# XBee-Explorer-Dongle-v14.net
KiCad netlist of a schematic drawn in EAGLE
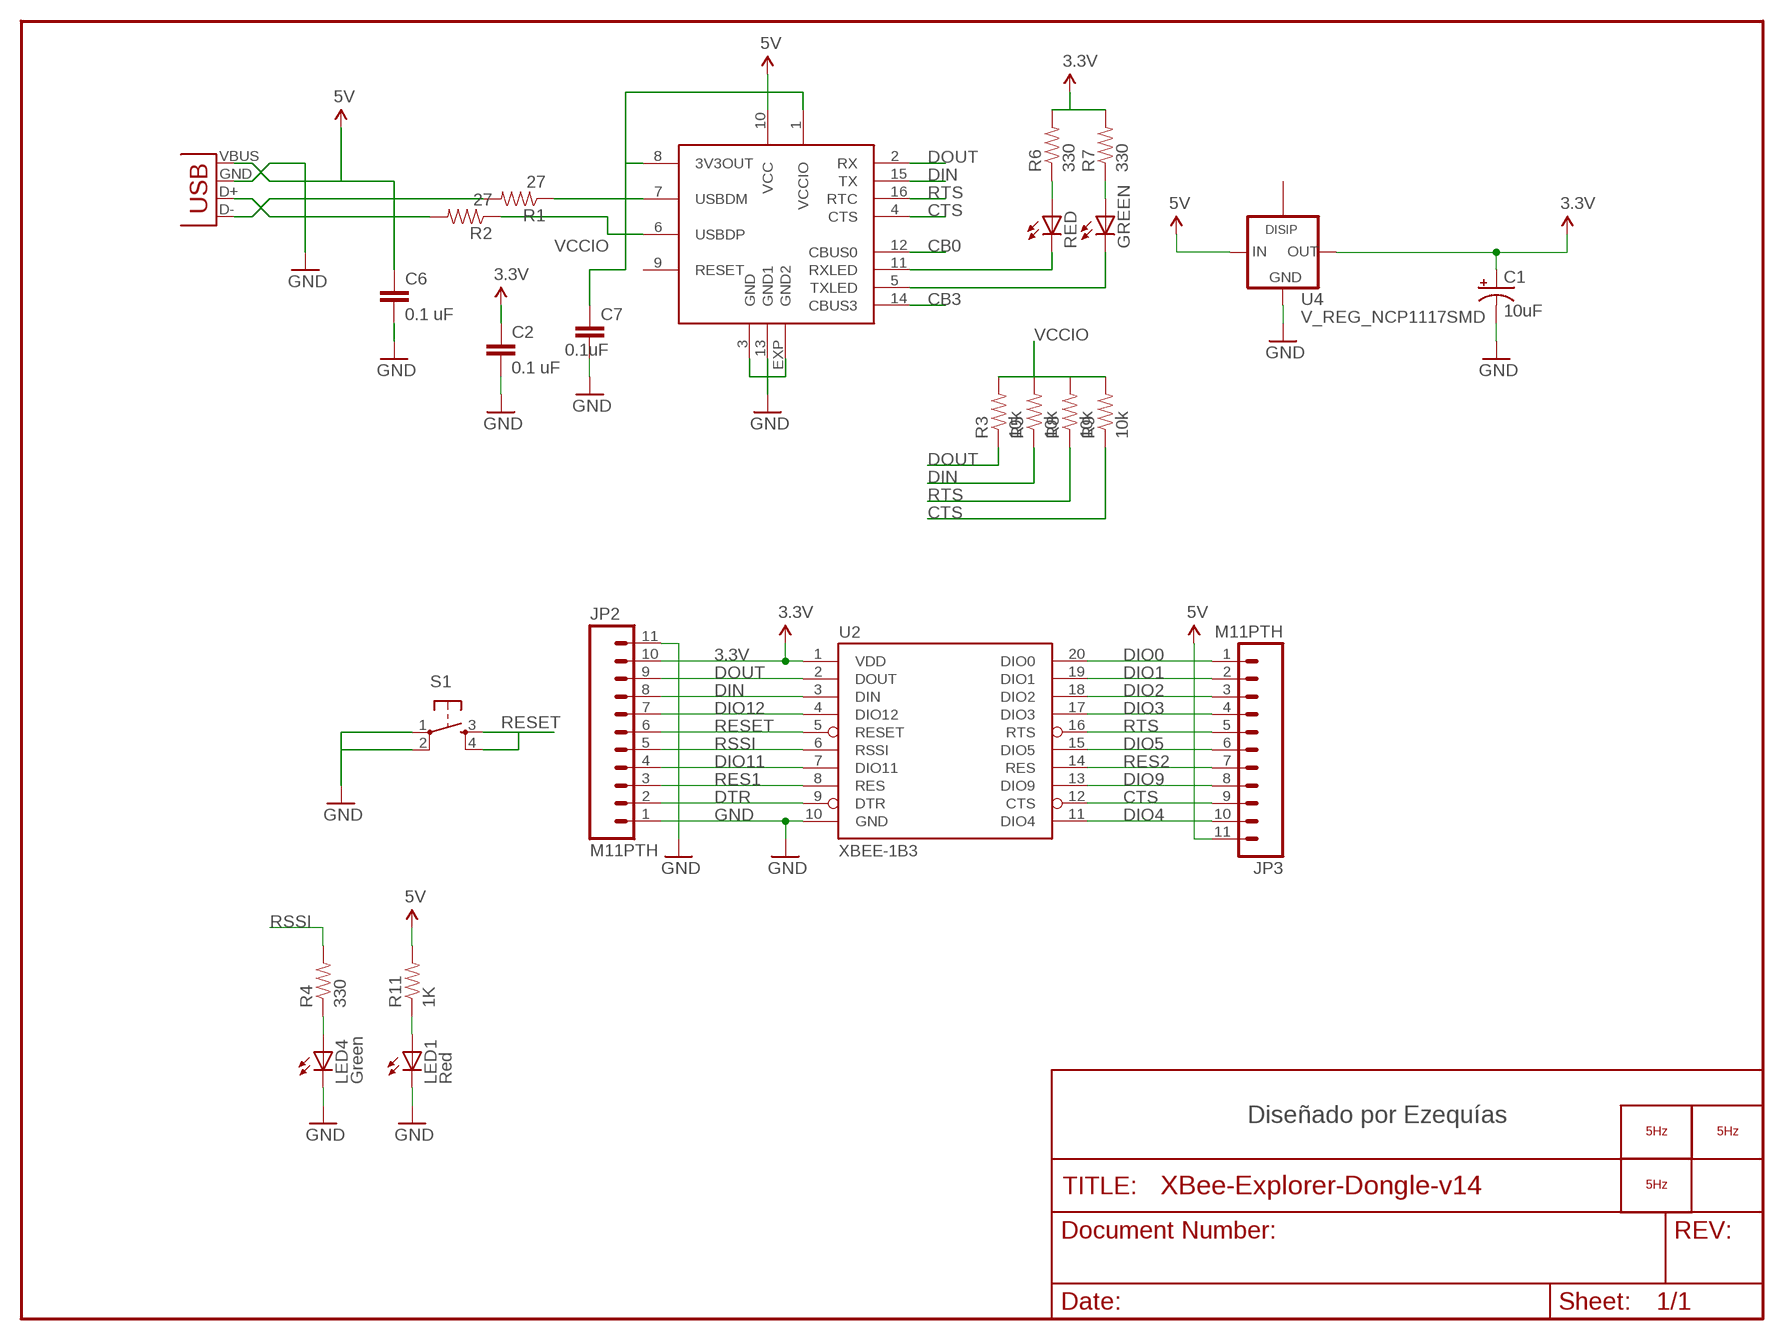
[diagram p0: schematic, sheet 1]

(export (version "E")
  (design (tool "Eeschema 10.0.6"))
  (components
    (comp (ref "C1")
      (value "10uF")
      (footprint "eagle-import:EIA3216")
      (libsource (lib "eagle-import") (part "CAP_POL1206"))
    )
    (comp (ref "C2")
      (value "0.1 uF")
      (footprint "eagle-import:0603-CAP")
      (libsource (lib "eagle-import") (part "CAP0603-CAP"))
    )
    (comp (ref "C6")
      (value "0.1 uF")
      (footprint "eagle-import:0603-CAP")
      (libsource (lib "eagle-import") (part "CAP0603-CAP"))
    )
    (comp (ref "C7")
      (value "0.1uF")
      (footprint "eagle-import:0603-CAP")
      (libsource (lib "eagle-import") (part "CAP0603-CAP"))
    )
    (comp (ref "GREEN")
      (value "LED0603")
      (footprint "eagle-import:LED-0603")
      (libsource (lib "eagle-import") (part "LED0603"))
    )
    (comp (ref "JP2")
      (value "M11PTH")
      (footprint "eagle-import:1X11")
      (libsource (lib "eagle-import") (part "M11PTH"))
    )
    (comp (ref "JP3")
      (value "M11PTH")
      (footprint "eagle-import:1X11")
      (libsource (lib "eagle-import") (part "M11PTH"))
    )
    (comp (ref "LED1")
      (value "Red")
      (footprint "eagle-import:LED-0603")
      (libsource (lib "eagle-import") (part "LED0603"))
    )
    (comp (ref "LED4")
      (value "Green")
      (footprint "eagle-import:LED-0603")
      (libsource (lib "eagle-import") (part "LED0603"))
    )
    (comp (ref "LOGO2")
      (value "LOGO_5HZ_H_10MM")
      (footprint "eagle-import:5HZ_LOGO_H_10MM")
      (libsource (lib "eagle-import") (part "LOGO_5HZ_H_10MM"))
    )
    (comp (ref "LOGO3")
      (value "LOGO_5HZ_H_COOPER_15MM")
      (footprint "eagle-import:5HZ_LOGO_H_COOPER_15MM")
      (libsource (lib "eagle-import") (part "LOGO_5HZ_H_COOPER_15MM"))
    )
    (comp (ref "LOGO4")
      (value "LOGO_5HZ_WEB_COOPER_10MM")
      (footprint "eagle-import:5HZ_WEB_COOPER_10MM")
      (libsource (lib "eagle-import") (part "LOGO_5HZ_WEB_COOPER_10MM"))
    )
    (comp (ref "R1")
      (value "27")
      (footprint "eagle-import:0603-RES")
      (libsource (lib "eagle-import") (part "RESISTOR0603-RES"))
    )
    (comp (ref "R2")
      (value "27")
      (footprint "eagle-import:0603-RES")
      (libsource (lib "eagle-import") (part "RESISTOR0603-RES"))
    )
    (comp (ref "R3")
      (value "10k")
      (footprint "eagle-import:0603-RES")
      (libsource (lib "eagle-import") (part "RESISTOR0603-RES"))
    )
    (comp (ref "R4")
      (value "330")
      (footprint "eagle-import:0603-RES")
      (libsource (lib "eagle-import") (part "RESISTOR0603-RES"))
    )
    (comp (ref "R5")
      (value "10k")
      (footprint "eagle-import:0603-RES")
      (libsource (lib "eagle-import") (part "RESISTOR0603-RES"))
    )
    (comp (ref "R6")
      (value "330")
      (footprint "eagle-import:0603-RES")
      (libsource (lib "eagle-import") (part "RESISTOR0603-RES"))
    )
    (comp (ref "R7")
      (value "330")
      (footprint "eagle-import:0603-RES")
      (libsource (lib "eagle-import") (part "RESISTOR0603-RES"))
    )
    (comp (ref "R8")
      (value "10k")
      (footprint "eagle-import:0603-RES")
      (libsource (lib "eagle-import") (part "RESISTOR0603-RES"))
    )
    (comp (ref "R9")
      (value "10k")
      (footprint "eagle-import:0603-RES")
      (libsource (lib "eagle-import") (part "RESISTOR0603-RES"))
    )
    (comp (ref "R11")
      (value "1K")
      (footprint "eagle-import:0603-RES")
      (libsource (lib "eagle-import") (part "RESISTOR0603-RES"))
    )
    (comp (ref "RED")
      (value "LED0603")
      (footprint "eagle-import:LED-0603")
      (libsource (lib "eagle-import") (part "LED0603"))
    )
    (comp (ref "S1")
      (value "TAC_SWITCHSMD")
      (footprint "eagle-import:TACTILE_SWITCH_SMD")
      (libsource (lib "eagle-import") (part "TAC_SWITCHSMD"))
    )
    (comp (ref "U$5")
      (value "FT230")
      (footprint "eagle-import:QFN-16")
      (libsource (lib "eagle-import") (part "FT230"))
    )
    (comp (ref "U2")
      (value "XBEE-1B3")
      (footprint "eagle-import:XBEE-SMD")
      (libsource (lib "eagle-import") (part "XBEE-1B3"))
    )
    (comp (ref "U4")
      (value "V_REG_NCP1117SMD")
      (footprint "eagle-import:SOT223")
      (libsource (lib "eagle-import") (part "V_REG_NCP1117SMD"))
    )
    (comp (ref "X2")
      (value "USB-A-H")
      (footprint "eagle-import:USB-A-H")
      (libsource (lib "eagle-import") (part "USB-A-H"))
    )
  )
  (nets
    (net (code "1") (name "/CB0") (class "Default")
      (node (ref "U$5") (pin "12") (pinfunction "CBUS0_12") (pintype "bidirectional"))
    )
    (net (code "2") (name "/CB3") (class "Default")
      (node (ref "U$5") (pin "14") (pinfunction "CBUS3_14") (pintype "bidirectional"))
    )
    (net (code "3") (name "/CTS") (class "Default")
      (node (ref "JP3") (pin "9") (pinfunction "9_9") (pintype "passive"))
      (node (ref "R9") (pin "1") (pinfunction "1_1") (pintype "passive"))
      (node (ref "U$5") (pin "4") (pinfunction "CTS_4") (pintype "bidirectional"))
      (node (ref "U2") (pin "12") (pinfunction "CTS_12") (pintype "output"))
    )
    (net (code "4") (name "/DIN") (class "Default")
      (node (ref "JP2") (pin "8") (pinfunction "8_8") (pintype "passive"))
      (node (ref "R5") (pin "1") (pinfunction "1_1") (pintype "passive"))
      (node (ref "U$5") (pin "15") (pinfunction "TX_15") (pintype "bidirectional"))
      (node (ref "U2") (pin "3") (pinfunction "DIN_3") (pintype "input"))
    )
    (net (code "5") (name "/DIO0") (class "Default")
      (node (ref "JP3") (pin "1") (pinfunction "1_1") (pintype "passive"))
      (node (ref "U2") (pin "20") (pinfunction "DIO0_20") (pintype "bidirectional"))
    )
    (net (code "6") (name "/DIO1") (class "Default")
      (node (ref "JP3") (pin "2") (pinfunction "2_2") (pintype "passive"))
      (node (ref "U2") (pin "19") (pinfunction "DIO1_19") (pintype "bidirectional"))
    )
    (net (code "7") (name "/DIO2") (class "Default")
      (node (ref "JP3") (pin "3") (pinfunction "3_3") (pintype "passive"))
      (node (ref "U2") (pin "18") (pinfunction "DIO2_18") (pintype "bidirectional"))
    )
    (net (code "8") (name "/DIO3") (class "Default")
      (node (ref "JP3") (pin "4") (pinfunction "4_4") (pintype "passive"))
      (node (ref "U2") (pin "17") (pinfunction "DIO3_17") (pintype "bidirectional"))
    )
    (net (code "9") (name "/DIO4") (class "Default")
      (node (ref "JP3") (pin "10") (pinfunction "10_10") (pintype "passive"))
      (node (ref "U2") (pin "11") (pinfunction "DIO4_11") (pintype "bidirectional"))
    )
    (net (code "10") (name "/DIO5") (class "Default")
      (node (ref "JP3") (pin "6") (pinfunction "6_6") (pintype "passive"))
      (node (ref "U2") (pin "15") (pinfunction "DIO5_15") (pintype "bidirectional"))
    )
    (net (code "11") (name "/DIO9") (class "Default")
      (node (ref "JP3") (pin "8") (pinfunction "8_8") (pintype "passive"))
      (node (ref "U2") (pin "13") (pinfunction "DIO9_13") (pintype "bidirectional"))
    )
    (net (code "12") (name "/DIO11") (class "Default")
      (node (ref "JP2") (pin "4") (pinfunction "4_4") (pintype "passive"))
      (node (ref "U2") (pin "7") (pinfunction "DIO11_7") (pintype "bidirectional"))
    )
    (net (code "13") (name "/DIO12") (class "Default")
      (node (ref "JP2") (pin "7") (pinfunction "7_7") (pintype "passive"))
      (node (ref "U2") (pin "4") (pinfunction "DIO12_4") (pintype "bidirectional"))
    )
    (net (code "14") (name "/DOUT") (class "Default")
      (node (ref "JP2") (pin "9") (pinfunction "9_9") (pintype "passive"))
      (node (ref "R3") (pin "1") (pinfunction "1_1") (pintype "passive"))
      (node (ref "U$5") (pin "2") (pinfunction "RX_2") (pintype "bidirectional"))
      (node (ref "U2") (pin "2") (pinfunction "DOUT_2") (pintype "output"))
    )
    (net (code "15") (name "/DTR") (class "Default")
      (node (ref "JP2") (pin "2") (pinfunction "2_2") (pintype "passive"))
      (node (ref "U2") (pin "9") (pinfunction "DTR_9") (pintype "bidirectional"))
    )
    (net (code "16") (name "/RES1") (class "Default")
      (node (ref "JP2") (pin "3") (pinfunction "3_3") (pintype "passive"))
      (node (ref "U2") (pin "8") (pinfunction "RES_8") (pintype "bidirectional"))
    )
    (net (code "17") (name "/RES2") (class "Default")
      (node (ref "JP3") (pin "7") (pinfunction "7_7") (pintype "passive"))
      (node (ref "U2") (pin "14") (pinfunction "RES_14") (pintype "bidirectional"))
    )
    (net (code "18") (name "/RESET") (class "Default")
      (node (ref "JP2") (pin "6") (pinfunction "6_6") (pintype "passive"))
      (node (ref "S1") (pin "3") (pinfunction "3_3") (pintype "passive"))
      (node (ref "S1") (pin "4") (pinfunction "4_4") (pintype "passive"))
      (node (ref "U2") (pin "5") (pinfunction "RESET_5") (pintype "input"))
    )
    (net (code "19") (name "/RSSI") (class "Default")
      (node (ref "JP2") (pin "5") (pinfunction "5_5") (pintype "passive"))
      (node (ref "R4") (pin "2") (pinfunction "2_2") (pintype "passive"))
      (node (ref "U2") (pin "6") (pinfunction "RSSI_6") (pintype "bidirectional"))
    )
    (net (code "20") (name "/RTS") (class "Default")
      (node (ref "JP3") (pin "5") (pinfunction "5_5") (pintype "passive"))
      (node (ref "R8") (pin "1") (pinfunction "1_1") (pintype "passive"))
      (node (ref "U$5") (pin "16") (pinfunction "RTC_16") (pintype "bidirectional"))
      (node (ref "U2") (pin "16") (pinfunction "RTS_16") (pintype "input"))
    )
    (net (code "21") (name "/VCCIO") (class "Default")
      (node (ref "C7") (pin "1") (pinfunction "1_1") (pintype "passive"))
      (node (ref "R3") (pin "2") (pinfunction "2_2") (pintype "passive"))
      (node (ref "R5") (pin "2") (pinfunction "2_2") (pintype "passive"))
      (node (ref "R8") (pin "2") (pinfunction "2_2") (pintype "passive"))
      (node (ref "R9") (pin "2") (pinfunction "2_2") (pintype "passive"))
      (node (ref "U$5") (pin "1") (pinfunction "VCCIO_1") (pintype "bidirectional"))
      (node (ref "U$5") (pin "8") (pinfunction "3V3OUT_8") (pintype "bidirectional"))
    )
    (net (code "22") (name "3.3V") (class "Default")
      (node (ref "C1") (pin "A") (pinfunction "+_A") (pintype "passive"))
      (node (ref "C2") (pin "1") (pinfunction "1_1") (pintype "passive"))
      (node (ref "JP2") (pin "10") (pinfunction "10_10") (pintype "passive"))
      (node (ref "R6") (pin "2") (pinfunction "2_2") (pintype "passive"))
      (node (ref "R7") (pin "2") (pinfunction "2_2") (pintype "passive"))
      (node (ref "U2") (pin "1") (pinfunction "VDD_1") (pintype "power_in"))
      (node (ref "U4") (pin "2") (pinfunction "OUT_2") (pintype "output"))
    )
    (net (code "23") (name "5V") (class "Default")
      (node (ref "C6") (pin "1") (pinfunction "1_1") (pintype "passive"))
      (node (ref "JP3") (pin "11") (pinfunction "11_11") (pintype "passive"))
      (node (ref "R11") (pin "2") (pinfunction "2_2") (pintype "passive"))
      (node (ref "U$5") (pin "10") (pinfunction "VCC_10") (pintype "bidirectional"))
      (node (ref "U4") (pin "3") (pinfunction "IN_3") (pintype "input"))
      (node (ref "X2") (pin "VBUS") (pinfunction "GND_VBUS") (pintype "bidirectional"))
    )
    (net (code "24") (name "GND") (class "Default")
      (node (ref "C1") (pin "C") (pinfunction "-_C") (pintype "passive"))
      (node (ref "C2") (pin "2") (pinfunction "2_2") (pintype "passive"))
      (node (ref "C6") (pin "2") (pinfunction "2_2") (pintype "passive"))
      (node (ref "C7") (pin "2") (pinfunction "2_2") (pintype "passive"))
      (node (ref "JP2") (pin "1") (pinfunction "1_1") (pintype "passive"))
      (node (ref "JP2") (pin "11") (pinfunction "11_11") (pintype "passive"))
      (node (ref "LED1") (pin "C") (pinfunction "C_C") (pintype "passive"))
      (node (ref "LED4") (pin "C") (pinfunction "C_C") (pintype "passive"))
      (node (ref "S1") (pin "1") (pinfunction "1_1") (pintype "passive"))
      (node (ref "S1") (pin "2") (pinfunction "2_2") (pintype "passive"))
      (node (ref "U$5") (pin "13") (pinfunction "GND1_13") (pintype "bidirectional"))
      (node (ref "U$5") (pin "3") (pinfunction "GND_3") (pintype "bidirectional"))
      (node (ref "U$5") (pin "EXP") (pinfunction "GND2_EXP") (pintype "bidirectional"))
      (node (ref "U2") (pin "10") (pinfunction "GND_10") (pintype "power_in"))
      (node (ref "U4") (pin "1") (pinfunction "GND_1") (pintype "input"))
      (node (ref "X2") (pin "GND") (pinfunction "VBUS_GND") (pintype "bidirectional"))
    )
    (net (code "25") (name "Net-(GREEN-PadA)") (class "Default")
      (node (ref "GREEN") (pin "A") (pinfunction "A_A") (pintype "passive"))
      (node (ref "R7") (pin "1") (pinfunction "1_1") (pintype "passive"))
    )
    (net (code "26") (name "Net-(LED1-PadA)") (class "Default")
      (node (ref "LED1") (pin "A") (pinfunction "A_A") (pintype "passive"))
      (node (ref "R11") (pin "1") (pinfunction "1_1") (pintype "passive"))
    )
    (net (code "27") (name "Net-(LED4-PadA)") (class "Default")
      (node (ref "LED4") (pin "A") (pinfunction "A_A") (pintype "passive"))
      (node (ref "R4") (pin "1") (pinfunction "1_1") (pintype "passive"))
    )
    (net (code "28") (name "Net-(R6-Pad1)") (class "Default")
      (node (ref "R6") (pin "1") (pinfunction "1_1") (pintype "passive"))
      (node (ref "RED") (pin "A") (pinfunction "A_A") (pintype "passive"))
    )
    (net (code "29") (name "Net-(U$5-RXLED)") (class "Default")
      (node (ref "RED") (pin "C") (pinfunction "C_C") (pintype "passive"))
      (node (ref "U$5") (pin "11") (pinfunction "RXLED_11") (pintype "bidirectional"))
    )
    (net (code "30") (name "Net-(U$5-TXLED)") (class "Default")
      (node (ref "GREEN") (pin "C") (pinfunction "C_C") (pintype "passive"))
      (node (ref "U$5") (pin "5") (pinfunction "TXLED_5") (pintype "bidirectional"))
    )
    (net (code "31") (name "Net-(U$5-USBDM)") (class "Default")
      (node (ref "R1") (pin "1") (pinfunction "1_1") (pintype "passive"))
      (node (ref "U$5") (pin "7") (pinfunction "USBDM_7") (pintype "bidirectional"))
    )
    (net (code "32") (name "Net-(U$5-USBDP)") (class "Default")
      (node (ref "R2") (pin "1") (pinfunction "1_1") (pintype "passive"))
      (node (ref "U$5") (pin "6") (pinfunction "USBDP_6") (pintype "bidirectional"))
    )
    (net (code "33") (name "Net-(X2-D+)") (class "Default")
      (node (ref "R1") (pin "2") (pinfunction "2_2") (pintype "passive"))
      (node (ref "X2") (pin "D-") (pinfunction "D+_D-") (pintype "bidirectional"))
    )
    (net (code "34") (name "Net-(X2-D-)") (class "Default")
      (node (ref "R2") (pin "2") (pinfunction "2_2") (pintype "passive"))
      (node (ref "X2") (pin "D+") (pinfunction "D-_D+") (pintype "bidirectional"))
    )
    (net (code "35") (name "unconnected-(U$5-RESET-Pad9)") (class "Default")
      (node (ref "U$5") (pin "9") (pinfunction "RESET_9") (pintype "bidirectional"))
    )
    (net (code "36") (name "unconnected-(U4-P$1-Pad4)") (class "Default")
      (node (ref "U4") (pin "4") (pinfunction "P$1_4") (pintype "bidirectional"))
    )
  )
)
